# Sheet3_-_Alimentations.net
KiCad netlist of a schematic drawn in Altium Designer
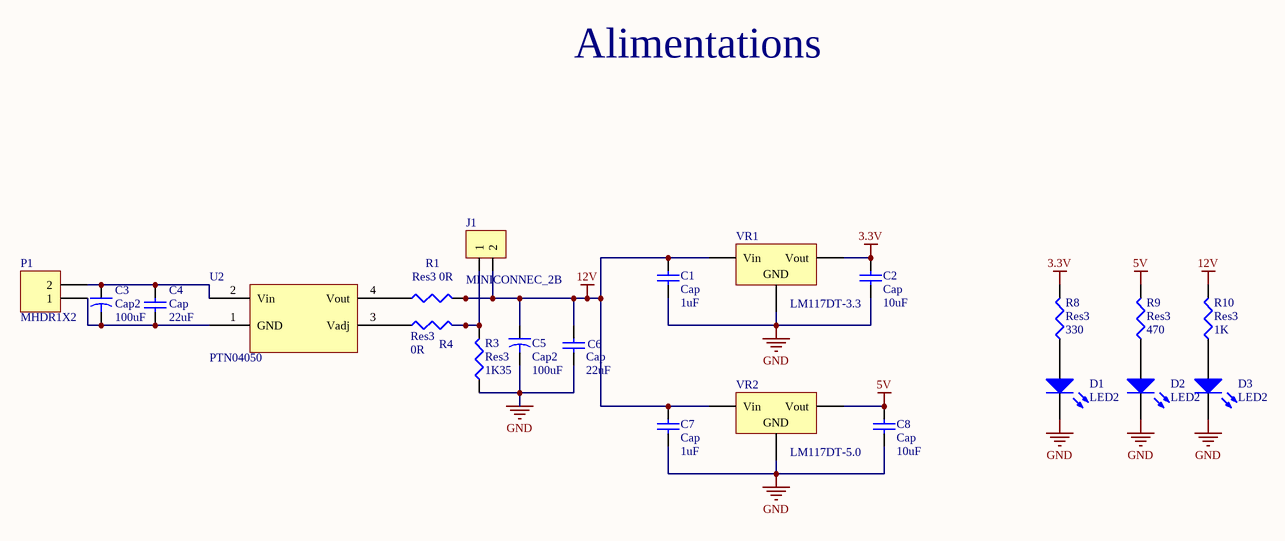
[diagram p0: Sheet3 - Alimentations.SchDoc]

(export (version "E")
  (design (tool "Eeschema 10.0.6"))
  (components
    (comp (ref "C1")
      (value "Cap")
      (footprint "RAD-0.3")
      (description "Capacitor")
      (fields (field (name "ALTIUM_VALUE") "1uF") (field (name "PUBLISHER") "Altium Limited"))
      (libsource (lib "Miscellaneous Devices") (part "Cap"))
    )
    (comp (ref "C2")
      (value "Cap")
      (footprint "RAD-0.3")
      (description "Capacitor")
      (fields (field (name "ALTIUM_VALUE") "10uF") (field (name "PUBLISHER") "Altium Limited"))
      (libsource (lib "Miscellaneous Devices") (part "Cap"))
    )
    (comp (ref "C3")
      (value "Cap2")
      (footprint "CAPR5-4X5")
      (description "Capacitor")
      (fields (field (name "ALTIUM_VALUE") "100uF") (field (name "PUBLISHER") "Altium Limited"))
      (libsource (lib "Miscellaneous Devices") (part "Cap2"))
    )
    (comp (ref "C4")
      (value "Cap")
      (footprint "RAD-0.3")
      (description "Capacitor")
      (fields (field (name "ALTIUM_VALUE") "22uF") (field (name "PUBLISHER") "Altium Limited"))
      (libsource (lib "Miscellaneous Devices") (part "Cap"))
    )
    (comp (ref "C5")
      (value "Cap2")
      (footprint "CAPR5-4X5")
      (description "Capacitor")
      (fields (field (name "ALTIUM_VALUE") "100uF") (field (name "PUBLISHER") "Altium Limited"))
      (libsource (lib "Miscellaneous Devices") (part "Cap2"))
    )
    (comp (ref "C6")
      (value "Cap")
      (footprint "RAD-0.3")
      (description "Capacitor")
      (fields (field (name "ALTIUM_VALUE") "22uF") (field (name "PUBLISHER") "Altium Limited"))
      (libsource (lib "Miscellaneous Devices") (part "Cap"))
    )
    (comp (ref "C7")
      (value "Cap")
      (footprint "RAD-0.3")
      (description "Capacitor")
      (fields (field (name "ALTIUM_VALUE") "1uF") (field (name "PUBLISHER") "Altium Limited"))
      (libsource (lib "Miscellaneous Devices") (part "Cap"))
    )
    (comp (ref "C8")
      (value "Cap")
      (footprint "RAD-0.3")
      (description "Capacitor")
      (fields (field (name "ALTIUM_VALUE") "10uF") (field (name "PUBLISHER") "Altium Limited"))
      (libsource (lib "Miscellaneous Devices") (part "Cap"))
    )
    (comp (ref "D1")
      (value "LED2")
      (footprint "DSO-F2/D6.1")
      (description "Typical RED, GREEN, YELLOW, AMBER GaAs LED")
      (fields (field (name "PUBLISHER") "Altium Limited"))
      (libsource (lib "Miscellaneous Devices") (part "LED2"))
    )
    (comp (ref "D2")
      (value "LED2")
      (footprint "DSO-F2/D6.1")
      (description "Typical RED, GREEN, YELLOW, AMBER GaAs LED")
      (fields (field (name "PUBLISHER") "Altium Limited"))
      (libsource (lib "Miscellaneous Devices") (part "LED2"))
    )
    (comp (ref "D3")
      (value "LED2")
      (footprint "DSO-F2/D6.1")
      (description "Typical RED, GREEN, YELLOW, AMBER GaAs LED")
      (fields (field (name "PUBLISHER") "Altium Limited"))
      (libsource (lib "Miscellaneous Devices") (part "LED2"))
    )
    (comp (ref "J1")
      (value "MINICONNEC_2B")
      (footprint "MINICONNEC_C")
      (description "Connecteur")
      (libsource (lib "lib_peb_1") (part "MINICONNEC_2B"))
    )
    (comp (ref "P1")
      (value "MHDR1X2")
      (footprint "MHDR1X2")
      (description "Header, 2-Pin")
      (fields (field (name "PUBLISHER") "Altium Limited"))
      (libsource (lib "Miscellaneous Connectors") (part "MHDR1X2"))
    )
    (comp (ref "R1")
      (value "Res3")
      (footprint "RESC1608L")
      (description "Resistor")
      (fields (field (name "ALTIUM_VALUE") "0R") (field (name "PUBLISHER") "Altium Limited"))
      (libsource (lib "Miscellaneous Devices") (part "Res3"))
    )
    (comp (ref "R3")
      (value "Res3")
      (footprint "RESC1608L")
      (description "Resistor")
      (fields (field (name "ALTIUM_VALUE") "1K35") (field (name "PUBLISHER") "Altium Limited"))
      (libsource (lib "Miscellaneous Devices") (part "Res3"))
    )
    (comp (ref "R4")
      (value "Res3")
      (footprint "RESC1608L")
      (description "Resistor")
      (fields (field (name "ALTIUM_VALUE") "0R") (field (name "PUBLISHER") "Altium Limited"))
      (libsource (lib "Miscellaneous Devices") (part "Res3"))
    )
    (comp (ref "R8")
      (value "Res3")
      (footprint "RESC1608L")
      (description "Resistor")
      (fields (field (name "ALTIUM_VALUE") "330") (field (name "PUBLISHER") "Altium Limited"))
      (libsource (lib "Miscellaneous Devices") (part "Res3"))
    )
    (comp (ref "R9")
      (value "Res3")
      (footprint "RESC1608L")
      (description "Resistor")
      (fields (field (name "ALTIUM_VALUE") "470") (field (name "PUBLISHER") "Altium Limited"))
      (libsource (lib "Miscellaneous Devices") (part "Res3"))
    )
    (comp (ref "R10")
      (value "Res3")
      (footprint "RESC1608L")
      (description "Resistor")
      (fields (field (name "ALTIUM_VALUE") "1K") (field (name "PUBLISHER") "Altium Limited"))
      (libsource (lib "Miscellaneous Devices") (part "Res3"))
    )
    (comp (ref "U2")
      (value "PTN04050")
      (footprint "PTN04050")
      (description "BOOST")
      (libsource (lib "lib_peb_1") (part "PTN04050"))
    )
    (comp (ref "VR1")
      (value "LM117DT-3.3")
      (footprint "TO254P1510-3_4N")
      (description "Voltage Regulator")
      (fields (field (name "PUBLISHER") "Altium Limited"))
      (libsource (lib "Miscellaneous Devices") (part "Volt Reg"))
    )
    (comp (ref "VR2")
      (value "LM117DT-5.0")
      (footprint "TO254P1510-3_4N")
      (description "Voltage Regulator")
      (fields (field (name "PUBLISHER") "Altium Limited"))
      (libsource (lib "Miscellaneous Devices") (part "Volt Reg"))
    )
  )
  (nets
    (net (code "1") (name "3.3V") (class "Default")
      (node (ref "C2") (pin "2") (pinfunction "2_2") (pintype "passive"))
      (node (ref "R8") (pin "2") (pinfunction "2_2") (pintype "passive"))
      (node (ref "VR1") (pin "3") (pinfunction "Vout_3") (pintype "passive"))
    )
    (net (code "2") (name "5V") (class "Default")
      (node (ref "C8") (pin "2") (pinfunction "2_2") (pintype "passive"))
      (node (ref "R9") (pin "2") (pinfunction "2_2") (pintype "passive"))
      (node (ref "VR2") (pin "3") (pinfunction "Vout_3") (pintype "passive"))
    )
    (net (code "3") (name "12V") (class "Default")
      (node (ref "C1") (pin "2") (pinfunction "2_2") (pintype "passive"))
      (node (ref "C5") (pin "1") (pinfunction "1_1") (pintype "passive"))
      (node (ref "C6") (pin "2") (pinfunction "2_2") (pintype "passive"))
      (node (ref "C7") (pin "2") (pinfunction "2_2") (pintype "passive"))
      (node (ref "J1") (pin "2") (pinfunction "2_2") (pintype "passive"))
      (node (ref "R1") (pin "2") (pinfunction "2_2") (pintype "passive"))
      (node (ref "R10") (pin "2") (pinfunction "2_2") (pintype "passive"))
      (node (ref "VR1") (pin "1") (pinfunction "Vin_1") (pintype "passive"))
      (node (ref "VR2") (pin "1") (pinfunction "Vin_1") (pintype "passive"))
    )
    (net (code "4") (name "GND") (class "Default")
      (node (ref "C1") (pin "1") (pinfunction "1_1") (pintype "passive"))
      (node (ref "C2") (pin "1") (pinfunction "1_1") (pintype "passive"))
      (node (ref "C5") (pin "2") (pinfunction "2_2") (pintype "passive"))
      (node (ref "C6") (pin "1") (pinfunction "1_1") (pintype "passive"))
      (node (ref "C7") (pin "1") (pinfunction "1_1") (pintype "passive"))
      (node (ref "C8") (pin "1") (pinfunction "1_1") (pintype "passive"))
      (node (ref "D1") (pin "2") (pinfunction "K_2") (pintype "passive"))
      (node (ref "D2") (pin "2") (pinfunction "K_2") (pintype "passive"))
      (node (ref "D3") (pin "2") (pinfunction "K_2") (pintype "passive"))
      (node (ref "R3") (pin "1") (pinfunction "1_1") (pintype "passive"))
      (node (ref "VR1") (pin "2") (pinfunction "GND_2") (pintype "passive"))
      (node (ref "VR2") (pin "2") (pinfunction "GND_2") (pintype "passive"))
    )
    (net (code "5") (name "Net-(D1-A)") (class "Default")
      (node (ref "D1") (pin "1") (pinfunction "A_1") (pintype "passive"))
      (node (ref "R8") (pin "1") (pinfunction "1_1") (pintype "passive"))
    )
    (net (code "6") (name "Net-(D2-A)") (class "Default")
      (node (ref "D2") (pin "1") (pinfunction "A_1") (pintype "passive"))
      (node (ref "R9") (pin "1") (pinfunction "1_1") (pintype "passive"))
    )
    (net (code "7") (name "Net-(D3-A)") (class "Default")
      (node (ref "D3") (pin "1") (pinfunction "A_1") (pintype "passive"))
      (node (ref "R10") (pin "1") (pinfunction "1_1") (pintype "passive"))
    )
    (net (code "8") (name "Net-(J1-Pad1)") (class "Default")
      (node (ref "J1") (pin "1") (pinfunction "1_1") (pintype "passive"))
      (node (ref "R3") (pin "2") (pinfunction "2_2") (pintype "passive"))
      (node (ref "R4") (pin "2") (pinfunction "2_2") (pintype "passive"))
    )
    (net (code "9") (name "Net-(U2-GND)") (class "Default")
      (node (ref "C3") (pin "2") (pinfunction "2_2") (pintype "passive"))
      (node (ref "C4") (pin "1") (pinfunction "1_1") (pintype "passive"))
      (node (ref "P1") (pin "1") (pinfunction "1_1") (pintype "passive"))
      (node (ref "U2") (pin "1") (pinfunction "GND_1") (pintype "passive"))
    )
    (net (code "10") (name "Net-(U2-Vadj)") (class "Default")
      (node (ref "R4") (pin "1") (pinfunction "1_1") (pintype "passive"))
      (node (ref "U2") (pin "3") (pinfunction "Vadj_3") (pintype "passive"))
    )
    (net (code "11") (name "Net-(U2-Vin)") (class "Default")
      (node (ref "C3") (pin "1") (pinfunction "1_1") (pintype "passive"))
      (node (ref "C4") (pin "2") (pinfunction "2_2") (pintype "passive"))
      (node (ref "P1") (pin "2") (pinfunction "2_2") (pintype "passive"))
      (node (ref "U2") (pin "2") (pinfunction "Vin_2") (pintype "passive"))
    )
    (net (code "12") (name "Net-(U2-Vout)") (class "Default")
      (node (ref "R1") (pin "1") (pinfunction "1_1") (pintype "passive"))
      (node (ref "U2") (pin "4") (pinfunction "Vout_4") (pintype "passive"))
    )
  )
)
